# LCD_TFT_Module.net
KiCad netlist of a schematic drawn in Altium Designer
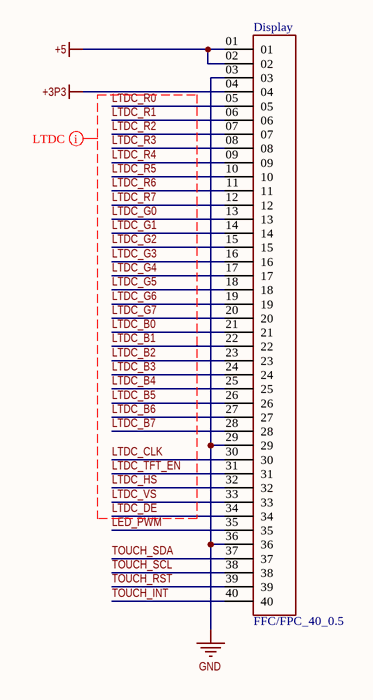
[diagram p0: LCD_TFT_Module.SchDoc]

(export (version "E")
  (design (tool "Eeschema 10.0.6"))
  (components
    (comp (ref "Display")
      (value "FFC/FPC_40_0.5")
      (footprint "FFC_40_0.5mm")
      (fields (field (name "MF") "Samtec") (field (name "MP") "ZF5S-40-02-T-WT"))
      (libsource (lib "Library") (part "FFC/FPC_40_0.5"))
    )
  )
  (nets
    (net (code "1") (name "+3P3") (class "Default")
      (node (ref "Display") (pin "04") (pinfunction "04_04") (pintype "passive"))
    )
    (net (code "2") (name "+5") (class "Default")
      (node (ref "Display") (pin "01") (pinfunction "01_01") (pintype "passive"))
      (node (ref "Display") (pin "02") (pinfunction "02_02") (pintype "passive"))
    )
    (net (code "3") (name "/LED_PWM") (class "Default")
      (node (ref "Display") (pin "35") (pinfunction "35_35") (pintype "passive"))
    )
    (net (code "4") (name "/LTDC_B0") (class "Default")
      (node (ref "Display") (pin "21") (pinfunction "21_21") (pintype "passive"))
    )
    (net (code "5") (name "/LTDC_B1") (class "Default")
      (node (ref "Display") (pin "22") (pinfunction "22_22") (pintype "passive"))
    )
    (net (code "6") (name "/LTDC_B2") (class "Default")
      (node (ref "Display") (pin "23") (pinfunction "23_23") (pintype "passive"))
    )
    (net (code "7") (name "/LTDC_B3") (class "Default")
      (node (ref "Display") (pin "24") (pinfunction "24_24") (pintype "passive"))
    )
    (net (code "8") (name "/LTDC_B4") (class "Default")
      (node (ref "Display") (pin "25") (pinfunction "25_25") (pintype "passive"))
    )
    (net (code "9") (name "/LTDC_B5") (class "Default")
      (node (ref "Display") (pin "26") (pinfunction "26_26") (pintype "passive"))
    )
    (net (code "10") (name "/LTDC_B6") (class "Default")
      (node (ref "Display") (pin "27") (pinfunction "27_27") (pintype "passive"))
    )
    (net (code "11") (name "/LTDC_B7") (class "Default")
      (node (ref "Display") (pin "28") (pinfunction "28_28") (pintype "passive"))
    )
    (net (code "12") (name "/LTDC_CLK") (class "Default")
      (node (ref "Display") (pin "30") (pinfunction "30_30") (pintype "passive"))
    )
    (net (code "13") (name "/LTDC_DE") (class "Default")
      (node (ref "Display") (pin "34") (pinfunction "34_34") (pintype "passive"))
    )
    (net (code "14") (name "/LTDC_G0") (class "Default")
      (node (ref "Display") (pin "13") (pinfunction "13_13") (pintype "passive"))
    )
    (net (code "15") (name "/LTDC_G1") (class "Default")
      (node (ref "Display") (pin "14") (pinfunction "14_14") (pintype "passive"))
    )
    (net (code "16") (name "/LTDC_G2") (class "Default")
      (node (ref "Display") (pin "15") (pinfunction "15_15") (pintype "passive"))
    )
    (net (code "17") (name "/LTDC_G3") (class "Default")
      (node (ref "Display") (pin "16") (pinfunction "16_16") (pintype "passive"))
    )
    (net (code "18") (name "/LTDC_G4") (class "Default")
      (node (ref "Display") (pin "17") (pinfunction "17_17") (pintype "passive"))
    )
    (net (code "19") (name "/LTDC_G5") (class "Default")
      (node (ref "Display") (pin "18") (pinfunction "18_18") (pintype "passive"))
    )
    (net (code "20") (name "/LTDC_G6") (class "Default")
      (node (ref "Display") (pin "19") (pinfunction "19_19") (pintype "passive"))
    )
    (net (code "21") (name "/LTDC_G7") (class "Default")
      (node (ref "Display") (pin "20") (pinfunction "20_20") (pintype "passive"))
    )
    (net (code "22") (name "/LTDC_HS") (class "Default")
      (node (ref "Display") (pin "32") (pinfunction "32_32") (pintype "passive"))
    )
    (net (code "23") (name "/LTDC_R0") (class "Default")
      (node (ref "Display") (pin "05") (pinfunction "05_05") (pintype "passive"))
    )
    (net (code "24") (name "/LTDC_R1") (class "Default")
      (node (ref "Display") (pin "06") (pinfunction "06_06") (pintype "passive"))
    )
    (net (code "25") (name "/LTDC_R2") (class "Default")
      (node (ref "Display") (pin "07") (pinfunction "07_07") (pintype "passive"))
    )
    (net (code "26") (name "/LTDC_R3") (class "Default")
      (node (ref "Display") (pin "08") (pinfunction "08_08") (pintype "passive"))
    )
    (net (code "27") (name "/LTDC_R4") (class "Default")
      (node (ref "Display") (pin "09") (pinfunction "09_09") (pintype "passive"))
    )
    (net (code "28") (name "/LTDC_R5") (class "Default")
      (node (ref "Display") (pin "10") (pinfunction "10_10") (pintype "passive"))
    )
    (net (code "29") (name "/LTDC_R6") (class "Default")
      (node (ref "Display") (pin "11") (pinfunction "11_11") (pintype "passive"))
    )
    (net (code "30") (name "/LTDC_R7") (class "Default")
      (node (ref "Display") (pin "12") (pinfunction "12_12") (pintype "passive"))
    )
    (net (code "31") (name "/LTDC_TFT_EN") (class "Default")
      (node (ref "Display") (pin "31") (pinfunction "31_31") (pintype "passive"))
    )
    (net (code "32") (name "/LTDC_VS") (class "Default")
      (node (ref "Display") (pin "33") (pinfunction "33_33") (pintype "passive"))
    )
    (net (code "33") (name "/TOUCH_INT") (class "Default")
      (node (ref "Display") (pin "40") (pinfunction "40_40") (pintype "passive"))
    )
    (net (code "34") (name "/TOUCH_RST") (class "Default")
      (node (ref "Display") (pin "39") (pinfunction "39_39") (pintype "passive"))
    )
    (net (code "35") (name "/TOUCH_SCL") (class "Default")
      (node (ref "Display") (pin "38") (pinfunction "38_38") (pintype "passive"))
    )
    (net (code "36") (name "/TOUCH_SDA") (class "Default")
      (node (ref "Display") (pin "37") (pinfunction "37_37") (pintype "passive"))
    )
    (net (code "37") (name "GND") (class "Default")
      (node (ref "Display") (pin "03") (pinfunction "03_03") (pintype "passive"))
      (node (ref "Display") (pin "29") (pinfunction "29_29") (pintype "passive"))
      (node (ref "Display") (pin "36") (pinfunction "36_36") (pintype "passive"))
    )
  )
)
